# TLC5928_Breakout_Board.net
KiCad netlist of a schematic drawn in EAGLE
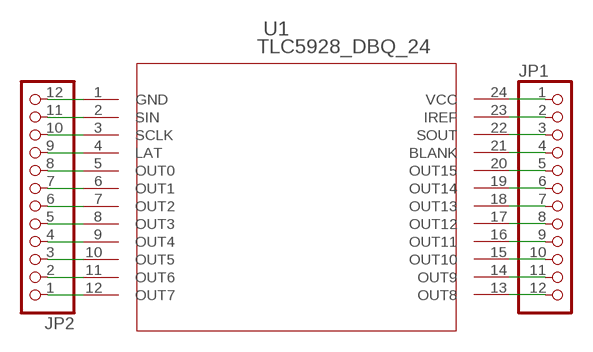
[diagram p0: schematic, sheet 1]

(export (version "E")
  (design (tool "Eeschema 10.0.6"))
  (components
    (comp (ref "JP1")
      (value "PINHD-1X12")
      (footprint "eagle-import:1X12")
      (libsource (lib "eagle-import") (part "PINHD-1X12"))
    )
    (comp (ref "JP2")
      (value "PINHD-1X12")
      (footprint "eagle-import:1X12")
      (libsource (lib "eagle-import") (part "PINHD-1X12"))
    )
    (comp (ref "U1")
      (value "TLC5928_DBQ_24")
      (footprint "eagle-import:DBQ24")
      (fields
        (field (name "GENERIC_PART_NUMBER") "TLC5928")
        (field (name "MANUFACTURER") "Texas Instruments")
        (field (name "MANUFACTURER_PART_NUMBER") "tlc5928_dbq_24")
      )
      (libsource (lib "eagle-import") (part "TLC5928_DBQ_24"))
    )
  )
  (nets
    (net (code "1") (name "Net-(U1-BLANK)") (class "Default")
      (node (ref "JP1") (pin "4") (pinfunction "4_4") (pintype "passive"))
      (node (ref "U1") (pin "21") (pinfunction "BLANK_21") (pintype "input"))
    )
    (net (code "2") (name "Net-(U1-GND)") (class "Default")
      (node (ref "JP2") (pin "12") (pinfunction "12_12") (pintype "passive"))
      (node (ref "U1") (pin "1") (pinfunction "GND_1") (pintype "power_in"))
    )
    (net (code "3") (name "Net-(U1-IREF)") (class "Default")
      (node (ref "JP1") (pin "2") (pinfunction "2_2") (pintype "passive"))
      (node (ref "U1") (pin "23") (pinfunction "IREF_23") (pintype "bidirectional"))
    )
    (net (code "4") (name "Net-(U1-LAT)") (class "Default")
      (node (ref "JP2") (pin "9") (pinfunction "9_9") (pintype "passive"))
      (node (ref "U1") (pin "4") (pinfunction "LAT_4") (pintype "input"))
    )
    (net (code "5") (name "Net-(U1-OUT0)") (class "Default")
      (node (ref "JP2") (pin "8") (pinfunction "8_8") (pintype "passive"))
      (node (ref "U1") (pin "5") (pinfunction "OUT0_5") (pintype "output"))
    )
    (net (code "6") (name "Net-(U1-OUT1)") (class "Default")
      (node (ref "JP2") (pin "7") (pinfunction "7_7") (pintype "passive"))
      (node (ref "U1") (pin "6") (pinfunction "OUT1_6") (pintype "output"))
    )
    (net (code "7") (name "Net-(U1-OUT2)") (class "Default")
      (node (ref "JP2") (pin "6") (pinfunction "6_6") (pintype "passive"))
      (node (ref "U1") (pin "7") (pinfunction "OUT2_7") (pintype "output"))
    )
    (net (code "8") (name "Net-(U1-OUT3)") (class "Default")
      (node (ref "JP2") (pin "5") (pinfunction "5_5") (pintype "passive"))
      (node (ref "U1") (pin "8") (pinfunction "OUT3_8") (pintype "output"))
    )
    (net (code "9") (name "Net-(U1-OUT4)") (class "Default")
      (node (ref "JP2") (pin "4") (pinfunction "4_4") (pintype "passive"))
      (node (ref "U1") (pin "9") (pinfunction "OUT4_9") (pintype "output"))
    )
    (net (code "10") (name "Net-(U1-OUT5)") (class "Default")
      (node (ref "JP2") (pin "3") (pinfunction "3_3") (pintype "passive"))
      (node (ref "U1") (pin "10") (pinfunction "OUT5_10") (pintype "output"))
    )
    (net (code "11") (name "Net-(U1-OUT6)") (class "Default")
      (node (ref "JP2") (pin "2") (pinfunction "2_2") (pintype "passive"))
      (node (ref "U1") (pin "11") (pinfunction "OUT6_11") (pintype "output"))
    )
    (net (code "12") (name "Net-(U1-OUT7)") (class "Default")
      (node (ref "JP2") (pin "1") (pinfunction "1_1") (pintype "passive"))
      (node (ref "U1") (pin "12") (pinfunction "OUT7_12") (pintype "output"))
    )
    (net (code "13") (name "Net-(U1-OUT8)") (class "Default")
      (node (ref "JP1") (pin "12") (pinfunction "12_12") (pintype "passive"))
      (node (ref "U1") (pin "13") (pinfunction "OUT8_13") (pintype "output"))
    )
    (net (code "14") (name "Net-(U1-OUT9)") (class "Default")
      (node (ref "JP1") (pin "11") (pinfunction "11_11") (pintype "passive"))
      (node (ref "U1") (pin "14") (pinfunction "OUT9_14") (pintype "output"))
    )
    (net (code "15") (name "Net-(U1-OUT10)") (class "Default")
      (node (ref "JP1") (pin "10") (pinfunction "10_10") (pintype "passive"))
      (node (ref "U1") (pin "15") (pinfunction "OUT10_15") (pintype "output"))
    )
    (net (code "16") (name "Net-(U1-OUT11)") (class "Default")
      (node (ref "JP1") (pin "9") (pinfunction "9_9") (pintype "passive"))
      (node (ref "U1") (pin "16") (pinfunction "OUT11_16") (pintype "output"))
    )
    (net (code "17") (name "Net-(U1-OUT12)") (class "Default")
      (node (ref "JP1") (pin "8") (pinfunction "8_8") (pintype "passive"))
      (node (ref "U1") (pin "17") (pinfunction "OUT12_17") (pintype "output"))
    )
    (net (code "18") (name "Net-(U1-OUT13)") (class "Default")
      (node (ref "JP1") (pin "7") (pinfunction "7_7") (pintype "passive"))
      (node (ref "U1") (pin "18") (pinfunction "OUT13_18") (pintype "output"))
    )
    (net (code "19") (name "Net-(U1-OUT14)") (class "Default")
      (node (ref "JP1") (pin "6") (pinfunction "6_6") (pintype "passive"))
      (node (ref "U1") (pin "19") (pinfunction "OUT14_19") (pintype "output"))
    )
    (net (code "20") (name "Net-(U1-OUT15)") (class "Default")
      (node (ref "JP1") (pin "5") (pinfunction "5_5") (pintype "passive"))
      (node (ref "U1") (pin "20") (pinfunction "OUT15_20") (pintype "output"))
    )
    (net (code "21") (name "Net-(U1-SCLK)") (class "Default")
      (node (ref "JP2") (pin "10") (pinfunction "10_10") (pintype "passive"))
      (node (ref "U1") (pin "3") (pinfunction "SCLK_3") (pintype "input"))
    )
    (net (code "22") (name "Net-(U1-SIN)") (class "Default")
      (node (ref "JP2") (pin "11") (pinfunction "11_11") (pintype "passive"))
      (node (ref "U1") (pin "2") (pinfunction "SIN_2") (pintype "input"))
    )
    (net (code "23") (name "Net-(U1-SOUT)") (class "Default")
      (node (ref "JP1") (pin "3") (pinfunction "3_3") (pintype "passive"))
      (node (ref "U1") (pin "22") (pinfunction "SOUT_22") (pintype "output"))
    )
    (net (code "24") (name "Net-(U1-VCC)") (class "Default")
      (node (ref "JP1") (pin "1") (pinfunction "1_1") (pintype "passive"))
      (node (ref "U1") (pin "24") (pinfunction "VCC_24") (pintype "power_in"))
    )
  )
)
